# QRcode.net
KiCad netlist of a schematic drawn in Altium Designer
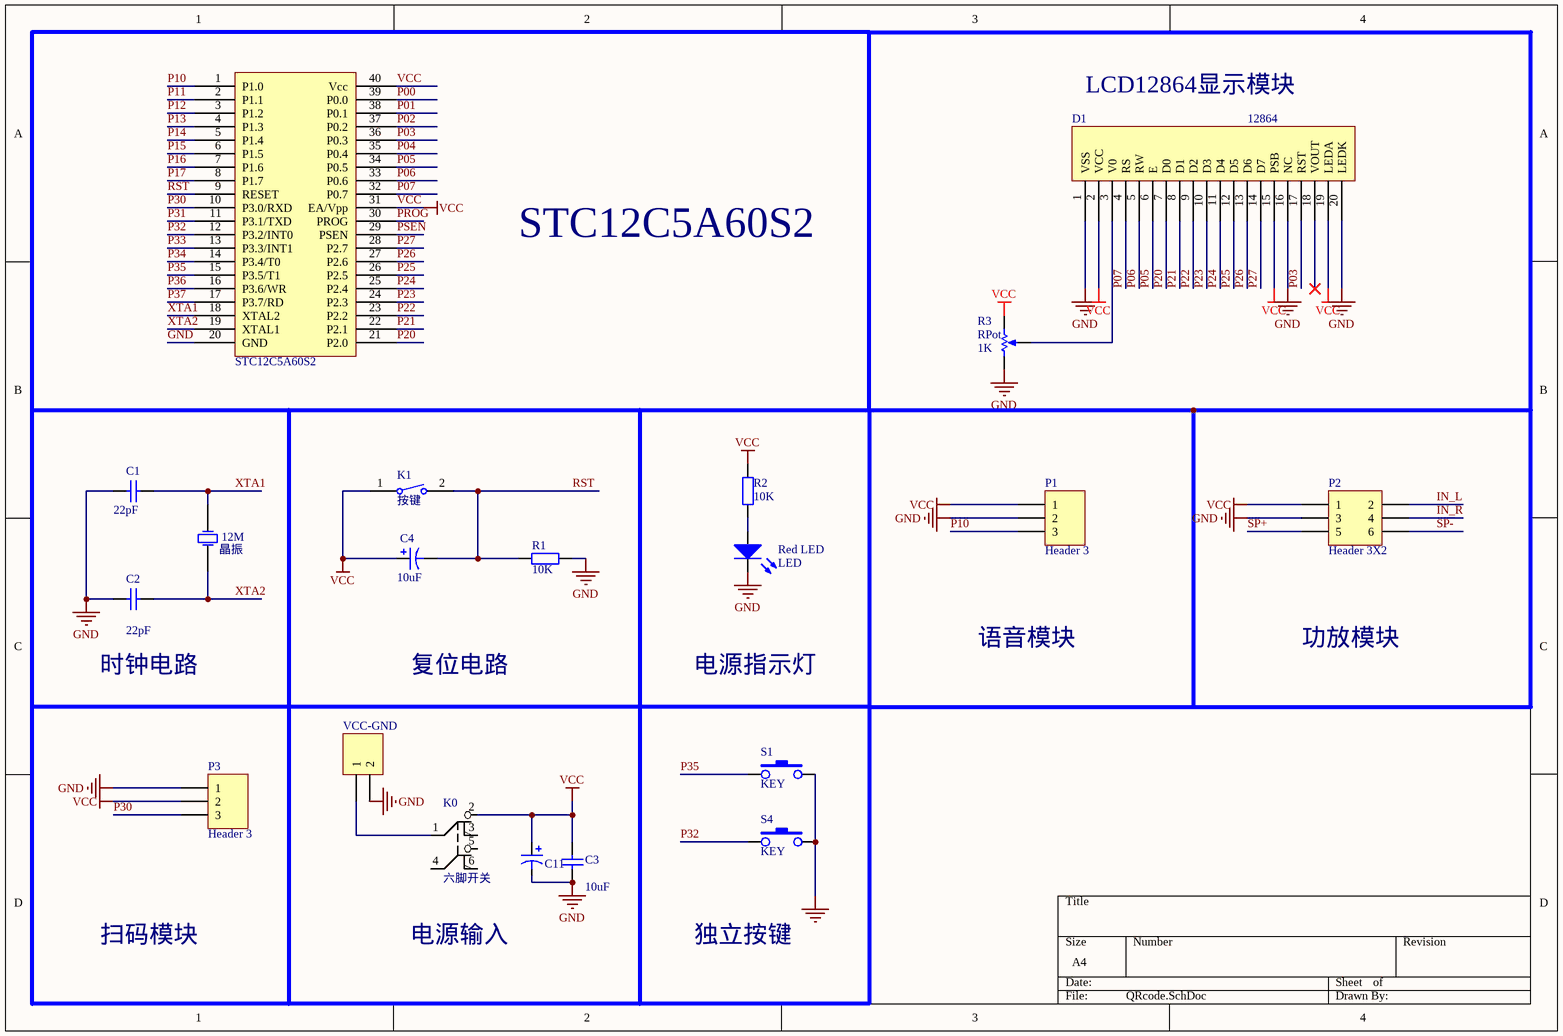
[diagram p0: QRcode.SchDoc]

(export (version "E")
  (design (tool "Eeschema 10.0.6"))
  (components
    (comp (ref "12M") (value "晶振") (footprint "晶振") (libsource (lib "Meter1.0（伟杰）") (part "晶振")))
    (comp (ref "C1")
      (value "22pF")
      (footprint "0805")
      (description "无极电容")
      (libsource (lib "JMU智能车专用") (part "Cap"))
    )
    (comp (ref "C2")
      (value "22pF")
      (footprint "0805")
      (description "无极电容")
      (libsource (lib "JMU智能车专用") (part "Cap"))
    )
    (comp (ref "C3")
      (value "10uF")
      (footprint "0805")
      (description "无极电容")
      (libsource (lib "JMU智能车专用") (part "Cap"))
    )
    (comp (ref "C4")
      (value "10uF")
      (footprint "RB7.6-15")
      (description "Polarized Capacitor (Radial)")
      (fields (field (name "Comment") "Cap Pol1") (field (name "PUBLISHER") "Altium Limited"))
      (libsource (lib "Miscellaneous Devices") (part "Cap Pol1"))
    )
    (comp (ref "C11")
      (value "100UF/470UF(封装慎选)")
      (footprint "ED6.3")
      (description "ED8:470UF  ED6.3:100UF")
      (libsource (lib "JMU智能车专用") (part "固态贴片电容"))
    )
    (comp (ref "D1") (value "12864") (footprint "SIP20") (libsource (lib "YLM") (part "12864")))
    (comp (ref "K0")
      (value "六脚开关")
      (footprint "按钮开关")
      (description "按钮开关")
      (libsource (lib "JMU智能车专用") (part "六脚开关"))
    )
    (comp (ref "K1") (value "按键") (footprint "按键") (libsource (lib "Meter1.0（伟杰）") (part "按键")))
    (comp (ref "P1")
      (value "Header 3")
      (footprint "HDR1X3")
      (description "Header, 3-Pin")
      (fields (field (name "PUBLISHER") "Altium Limited"))
      (libsource (lib "Miscellaneous Connectors") (part "Header 3"))
    )
    (comp (ref "P2")
      (value "Header 3X2")
      (footprint "HDR2X3")
      (description "Header, 3-Pin, Dual row")
      (fields (field (name "PUBLISHER") "Altium Limited"))
      (libsource (lib "Miscellaneous Connectors") (part "Header 3X2"))
    )
    (comp (ref "P3")
      (value "Header 3")
      (footprint "HDR1X3")
      (description "Header, 3-Pin")
      (fields (field (name "PUBLISHER") "Altium Limited"))
      (libsource (lib "Miscellaneous Connectors") (part "Header 3"))
    )
    (comp (ref "R1")
      (value "10K")
      (footprint "0805")
      (description "通用电阻")
      (libsource (lib "") (part "Res_1"))
    )
    (comp (ref "R2")
      (value "10K")
      (footprint "0805")
      (description "通用电阻")
      (libsource (lib "JMU智能车专用") (part "Res"))
    )
    (comp (ref "R3")
      (value "RPot")
      (footprint "VR5")
      (description "Potentiometer")
      (fields (field (name "ALTIUM_VALUE") "1K") (field (name "PUBLISHER") "Altium Limited"))
      (libsource (lib "Miscellaneous Devices") (part "RPot"))
    )
    (comp (ref "Red LED")
      (value "LED")
      (footprint "LED(0805)")
      (description "发光二极管")
      (libsource (lib "JMU智能车专用") (part "LED"))
    )
    (comp (ref "S1") (value "KEY") (footprint "SWITCH") (libsource (lib "常用元件库") (part "KEY")))
    (comp (ref "S4") (value "KEY") (footprint "SWITCH") (libsource (lib "常用元件库") (part "KEY")))
    (comp (ref "STC89C52")
      (value "STC12C5A60S2")
      (footprint "89C51")
      (libsource (lib "89C51芯片") (part "Component_1"))
    )
    (comp (ref "VCC-GND")
      (value "~")
      (footprint "HDR1X2")
      (description "Header, 2-Pin")
      (fields (field (name "PUBLISHER") "Altium Limited"))
      (libsource (lib "Miscellaneous Connectors") (part "Header 2"))
    )
  )
  (nets
    (net (code "1") (name "/IN_L") (class "Default")
      (node (ref "P2") (pin "2") (pinfunction "2_2") (pintype "passive"))
    )
    (net (code "2") (name "/IN_R") (class "Default")
      (node (ref "P2") (pin "4") (pinfunction "4_4") (pintype "passive"))
    )
    (net (code "3") (name "/P00") (class "Default")
      (node (ref "STC89C52") (pin "39") (pinfunction "P0.0_39") (pintype "passive"))
    )
    (net (code "4") (name "/P01") (class "Default")
      (node (ref "STC89C52") (pin "38") (pinfunction "P0.1_38") (pintype "passive"))
    )
    (net (code "5") (name "/P02") (class "Default")
      (node (ref "STC89C52") (pin "37") (pinfunction "P0.2_37") (pintype "passive"))
    )
    (net (code "6") (name "/P03") (class "Default")
      (node (ref "D1") (pin "17") (pinfunction "RST_17") (pintype "passive"))
      (node (ref "STC89C52") (pin "36") (pinfunction "P0.3_36") (pintype "passive"))
    )
    (net (code "7") (name "/P04") (class "Default")
      (node (ref "STC89C52") (pin "35") (pinfunction "P0.4_35") (pintype "passive"))
    )
    (net (code "8") (name "/P05") (class "Default")
      (node (ref "D1") (pin "6") (pinfunction "E_6") (pintype "passive"))
      (node (ref "STC89C52") (pin "34") (pinfunction "P0.5_34") (pintype "passive"))
    )
    (net (code "9") (name "/P06") (class "Default")
      (node (ref "D1") (pin "5") (pinfunction "RW_5") (pintype "passive"))
      (node (ref "STC89C52") (pin "33") (pinfunction "P0.6_33") (pintype "passive"))
    )
    (net (code "10") (name "/P07") (class "Default")
      (node (ref "D1") (pin "4") (pinfunction "RS_4") (pintype "passive"))
      (node (ref "STC89C52") (pin "32") (pinfunction "P0.7_32") (pintype "passive"))
    )
    (net (code "11") (name "/P10") (class "Default")
      (node (ref "P1") (pin "3") (pinfunction "3_3") (pintype "passive"))
      (node (ref "STC89C52") (pin "1") (pinfunction "P1.0_1") (pintype "passive"))
    )
    (net (code "12") (name "/P11") (class "Default")
      (node (ref "STC89C52") (pin "2") (pinfunction "P1.1_2") (pintype "passive"))
    )
    (net (code "13") (name "/P12") (class "Default")
      (node (ref "STC89C52") (pin "3") (pinfunction "P1.2_3") (pintype "passive"))
    )
    (net (code "14") (name "/P13") (class "Default")
      (node (ref "STC89C52") (pin "4") (pinfunction "P1.3_4") (pintype "passive"))
    )
    (net (code "15") (name "/P14") (class "Default")
      (node (ref "STC89C52") (pin "5") (pinfunction "P1.4_5") (pintype "passive"))
    )
    (net (code "16") (name "/P15") (class "Default")
      (node (ref "STC89C52") (pin "6") (pinfunction "P1.5_6") (pintype "passive"))
    )
    (net (code "17") (name "/P16") (class "Default")
      (node (ref "STC89C52") (pin "7") (pinfunction "P1.6_7") (pintype "passive"))
    )
    (net (code "18") (name "/P17") (class "Default")
      (node (ref "STC89C52") (pin "8") (pinfunction "P1.7_8") (pintype "passive"))
    )
    (net (code "19") (name "/P20") (class "Default")
      (node (ref "D1") (pin "7") (pinfunction "D0_7") (pintype "passive"))
      (node (ref "STC89C52") (pin "21") (pinfunction "P2.0_21") (pintype "passive"))
    )
    (net (code "20") (name "/P21") (class "Default")
      (node (ref "D1") (pin "8") (pinfunction "D1_8") (pintype "passive"))
      (node (ref "STC89C52") (pin "22") (pinfunction "P2.1_22") (pintype "passive"))
    )
    (net (code "21") (name "/P22") (class "Default")
      (node (ref "D1") (pin "9") (pinfunction "D2_9") (pintype "passive"))
      (node (ref "STC89C52") (pin "23") (pinfunction "P2.2_23") (pintype "passive"))
    )
    (net (code "22") (name "/P23") (class "Default")
      (node (ref "D1") (pin "10") (pinfunction "D3_10") (pintype "passive"))
      (node (ref "STC89C52") (pin "24") (pinfunction "P2.3_24") (pintype "passive"))
    )
    (net (code "23") (name "/P24") (class "Default")
      (node (ref "D1") (pin "11") (pinfunction "D4_11") (pintype "passive"))
      (node (ref "STC89C52") (pin "25") (pinfunction "P2.4_25") (pintype "passive"))
    )
    (net (code "24") (name "/P25") (class "Default")
      (node (ref "D1") (pin "12") (pinfunction "D5_12") (pintype "passive"))
      (node (ref "STC89C52") (pin "26") (pinfunction "P2.5_26") (pintype "passive"))
    )
    (net (code "25") (name "/P26") (class "Default")
      (node (ref "D1") (pin "13") (pinfunction "D6_13") (pintype "passive"))
      (node (ref "STC89C52") (pin "27") (pinfunction "P2.6_27") (pintype "passive"))
    )
    (net (code "26") (name "/P27") (class "Default")
      (node (ref "D1") (pin "14") (pinfunction "D7_14") (pintype "passive"))
      (node (ref "STC89C52") (pin "28") (pinfunction "P2.7_28") (pintype "passive"))
    )
    (net (code "27") (name "/P30") (class "Default")
      (node (ref "P3") (pin "3") (pinfunction "3_3") (pintype "passive"))
      (node (ref "STC89C52") (pin "10") (pinfunction "P3.0/RXD_10") (pintype "passive"))
    )
    (net (code "28") (name "/P31") (class "Default")
      (node (ref "STC89C52") (pin "11") (pinfunction "P3.1/TXD_11") (pintype "passive"))
    )
    (net (code "29") (name "/P32") (class "Default")
      (node (ref "S4") (pin "1") (pinfunction "1_1") (pintype "passive"))
      (node (ref "STC89C52") (pin "12") (pinfunction "P3.2/INT0_12") (pintype "passive"))
    )
    (net (code "30") (name "/P33") (class "Default")
      (node (ref "STC89C52") (pin "13") (pinfunction "P3.3/INT1_13") (pintype "passive"))
    )
    (net (code "31") (name "/P34") (class "Default")
      (node (ref "STC89C52") (pin "14") (pinfunction "P3.4/T0_14") (pintype "passive"))
    )
    (net (code "32") (name "/P35") (class "Default")
      (node (ref "S1") (pin "1") (pinfunction "1_1") (pintype "passive"))
      (node (ref "STC89C52") (pin "15") (pinfunction "P3.5/T1_15") (pintype "passive"))
    )
    (net (code "33") (name "/P36") (class "Default")
      (node (ref "STC89C52") (pin "16") (pinfunction "P3.6/WR_16") (pintype "passive"))
    )
    (net (code "34") (name "/P37") (class "Default")
      (node (ref "STC89C52") (pin "17") (pinfunction "P3.7/RD_17") (pintype "passive"))
    )
    (net (code "35") (name "/PROG") (class "Default")
      (node (ref "STC89C52") (pin "30") (pinfunction "PROG_30") (pintype "passive"))
    )
    (net (code "36") (name "/PSEN") (class "Default")
      (node (ref "STC89C52") (pin "29") (pinfunction "PSEN_29") (pintype "passive"))
    )
    (net (code "37") (name "/RST") (class "Default")
      (node (ref "C4") (pin "2") (pinfunction "2_2") (pintype "passive"))
      (node (ref "K1") (pin "2") (pinfunction "2_2") (pintype "passive"))
      (node (ref "R1") (pin "1") (pinfunction "1_1") (pintype "passive"))
      (node (ref "STC89C52") (pin "9") (pinfunction "RESET_9") (pintype "passive"))
    )
    (net (code "38") (name "/SP+") (class "Default")
      (node (ref "P2") (pin "5") (pinfunction "5_5") (pintype "passive"))
    )
    (net (code "39") (name "/SP-") (class "Default")
      (node (ref "P2") (pin "6") (pinfunction "6_6") (pintype "passive"))
    )
    (net (code "40") (name "/XTA1") (class "Default")
      (node (ref "12M") (pin "2") (pinfunction "2_2") (pintype "passive"))
      (node (ref "C1") (pin "2") (pinfunction "2_2") (pintype "passive"))
      (node (ref "STC89C52") (pin "18") (pinfunction "XTAL2_18") (pintype "passive"))
    )
    (net (code "41") (name "/XTA2") (class "Default")
      (node (ref "12M") (pin "1") (pinfunction "1_1") (pintype "passive"))
      (node (ref "C2") (pin "2") (pinfunction "2_2") (pintype "passive"))
      (node (ref "STC89C52") (pin "19") (pinfunction "XTAL1_19") (pintype "passive"))
    )
    (net (code "42") (name "GND") (class "Default")
      (node (ref "C1") (pin "1") (pinfunction "1_1") (pintype "passive"))
      (node (ref "C11") (pin "2") (pinfunction "2_2") (pintype "passive"))
      (node (ref "C2") (pin "1") (pinfunction "1_1") (pintype "passive"))
      (node (ref "C3") (pin "1") (pinfunction "1_1") (pintype "passive"))
      (node (ref "D1") (pin "1") (pinfunction "VSS_1") (pintype "passive"))
      (node (ref "D1") (pin "16") (pinfunction "NC_16") (pintype "passive"))
      (node (ref "D1") (pin "20") (pinfunction "LEDK_20") (pintype "passive"))
      (node (ref "P1") (pin "2") (pinfunction "2_2") (pintype "passive"))
      (node (ref "P2") (pin "3") (pinfunction "3_3") (pintype "passive"))
      (node (ref "P3") (pin "1") (pinfunction "1_1") (pintype "passive"))
      (node (ref "R1") (pin "2") (pinfunction "2_2") (pintype "passive"))
      (node (ref "R3") (pin "1") (pinfunction "TOP_1") (pintype "passive"))
      (node (ref "Red LED") (pin "2") (pinfunction "K_2") (pintype "passive"))
      (node (ref "S1") (pin "2") (pinfunction "2_2") (pintype "passive"))
      (node (ref "S4") (pin "2") (pinfunction "2_2") (pintype "passive"))
      (node (ref "STC89C52") (pin "20") (pinfunction "GND_20") (pintype "passive"))
      (node (ref "VCC-GND") (pin "2") (pinfunction "2_2") (pintype "passive"))
    )
    (net (code "43") (name "Net-(D1-V0)") (class "Default")
      (node (ref "D1") (pin "3") (pinfunction "V0_3") (pintype "passive"))
      (node (ref "R3") (pin "3") (pinfunction "TAP_3") (pintype "passive"))
    )
    (net (code "44") (name "Net-(K0-Pad1)") (class "Default")
      (node (ref "K0") (pin "1") (pinfunction "1_1") (pintype "power_in"))
      (node (ref "VCC-GND") (pin "1") (pinfunction "1_1") (pintype "passive"))
    )
    (net (code "45") (name "Net-(Red LED-A)") (class "Default")
      (node (ref "R2") (pin "1") (pinfunction "1_1") (pintype "passive"))
      (node (ref "Red LED") (pin "1") (pinfunction "A_1") (pintype "passive"))
    )
    (net (code "46") (name "VCC") (class "Default")
      (node (ref "C11") (pin "1") (pinfunction "1_1") (pintype "passive"))
      (node (ref "C3") (pin "2") (pinfunction "2_2") (pintype "passive"))
      (node (ref "C4") (pin "1") (pinfunction "1_1") (pintype "passive"))
      (node (ref "D1") (pin "15") (pinfunction "PSB_15") (pintype "passive"))
      (node (ref "D1") (pin "19") (pinfunction "LEDA_19") (pintype "passive"))
      (node (ref "D1") (pin "2") (pinfunction "VCC_2") (pintype "passive"))
      (node (ref "K0") (pin "2") (pinfunction "2_2") (pintype "power_in"))
      (node (ref "K1") (pin "1") (pinfunction "1_1") (pintype "passive"))
      (node (ref "P1") (pin "1") (pinfunction "1_1") (pintype "passive"))
      (node (ref "P2") (pin "1") (pinfunction "1_1") (pintype "passive"))
      (node (ref "P3") (pin "2") (pinfunction "2_2") (pintype "passive"))
      (node (ref "R2") (pin "2") (pinfunction "2_2") (pintype "passive"))
      (node (ref "R3") (pin "2") (pinfunction "BOT_2") (pintype "passive"))
      (node (ref "STC89C52") (pin "31") (pinfunction "EA/Vpp_31") (pintype "passive"))
      (node (ref "STC89C52") (pin "40") (pinfunction "Vcc_40") (pintype "passive"))
    )
    (net (code "47") (name "unconnected-(D1-VOUT-Pad18)") (class "Default")
      (node (ref "D1") (pin "18") (pinfunction "VOUT_18") (pintype "passive+no_connect"))
    )
    (net (code "48") (name "unconnected-(K0-Pad3)") (class "Default")
      (node (ref "K0") (pin "3") (pinfunction "3_3") (pintype "power_in"))
    )
    (net (code "49") (name "unconnected-(K0-Pad4)") (class "Default")
      (node (ref "K0") (pin "4") (pinfunction "4_4") (pintype "power_in"))
    )
    (net (code "50") (name "unconnected-(K0-Pad5)") (class "Default")
      (node (ref "K0") (pin "5") (pinfunction "5_5") (pintype "power_in"))
    )
    (net (code "51") (name "unconnected-(K0-Pad6)") (class "Default")
      (node (ref "K0") (pin "6") (pinfunction "6_6") (pintype "power_in"))
    )
  )
)
